# IoT_Greenhouse_V1_0_A_-_Esp32.net
KiCad netlist of a schematic drawn in Altium Designer
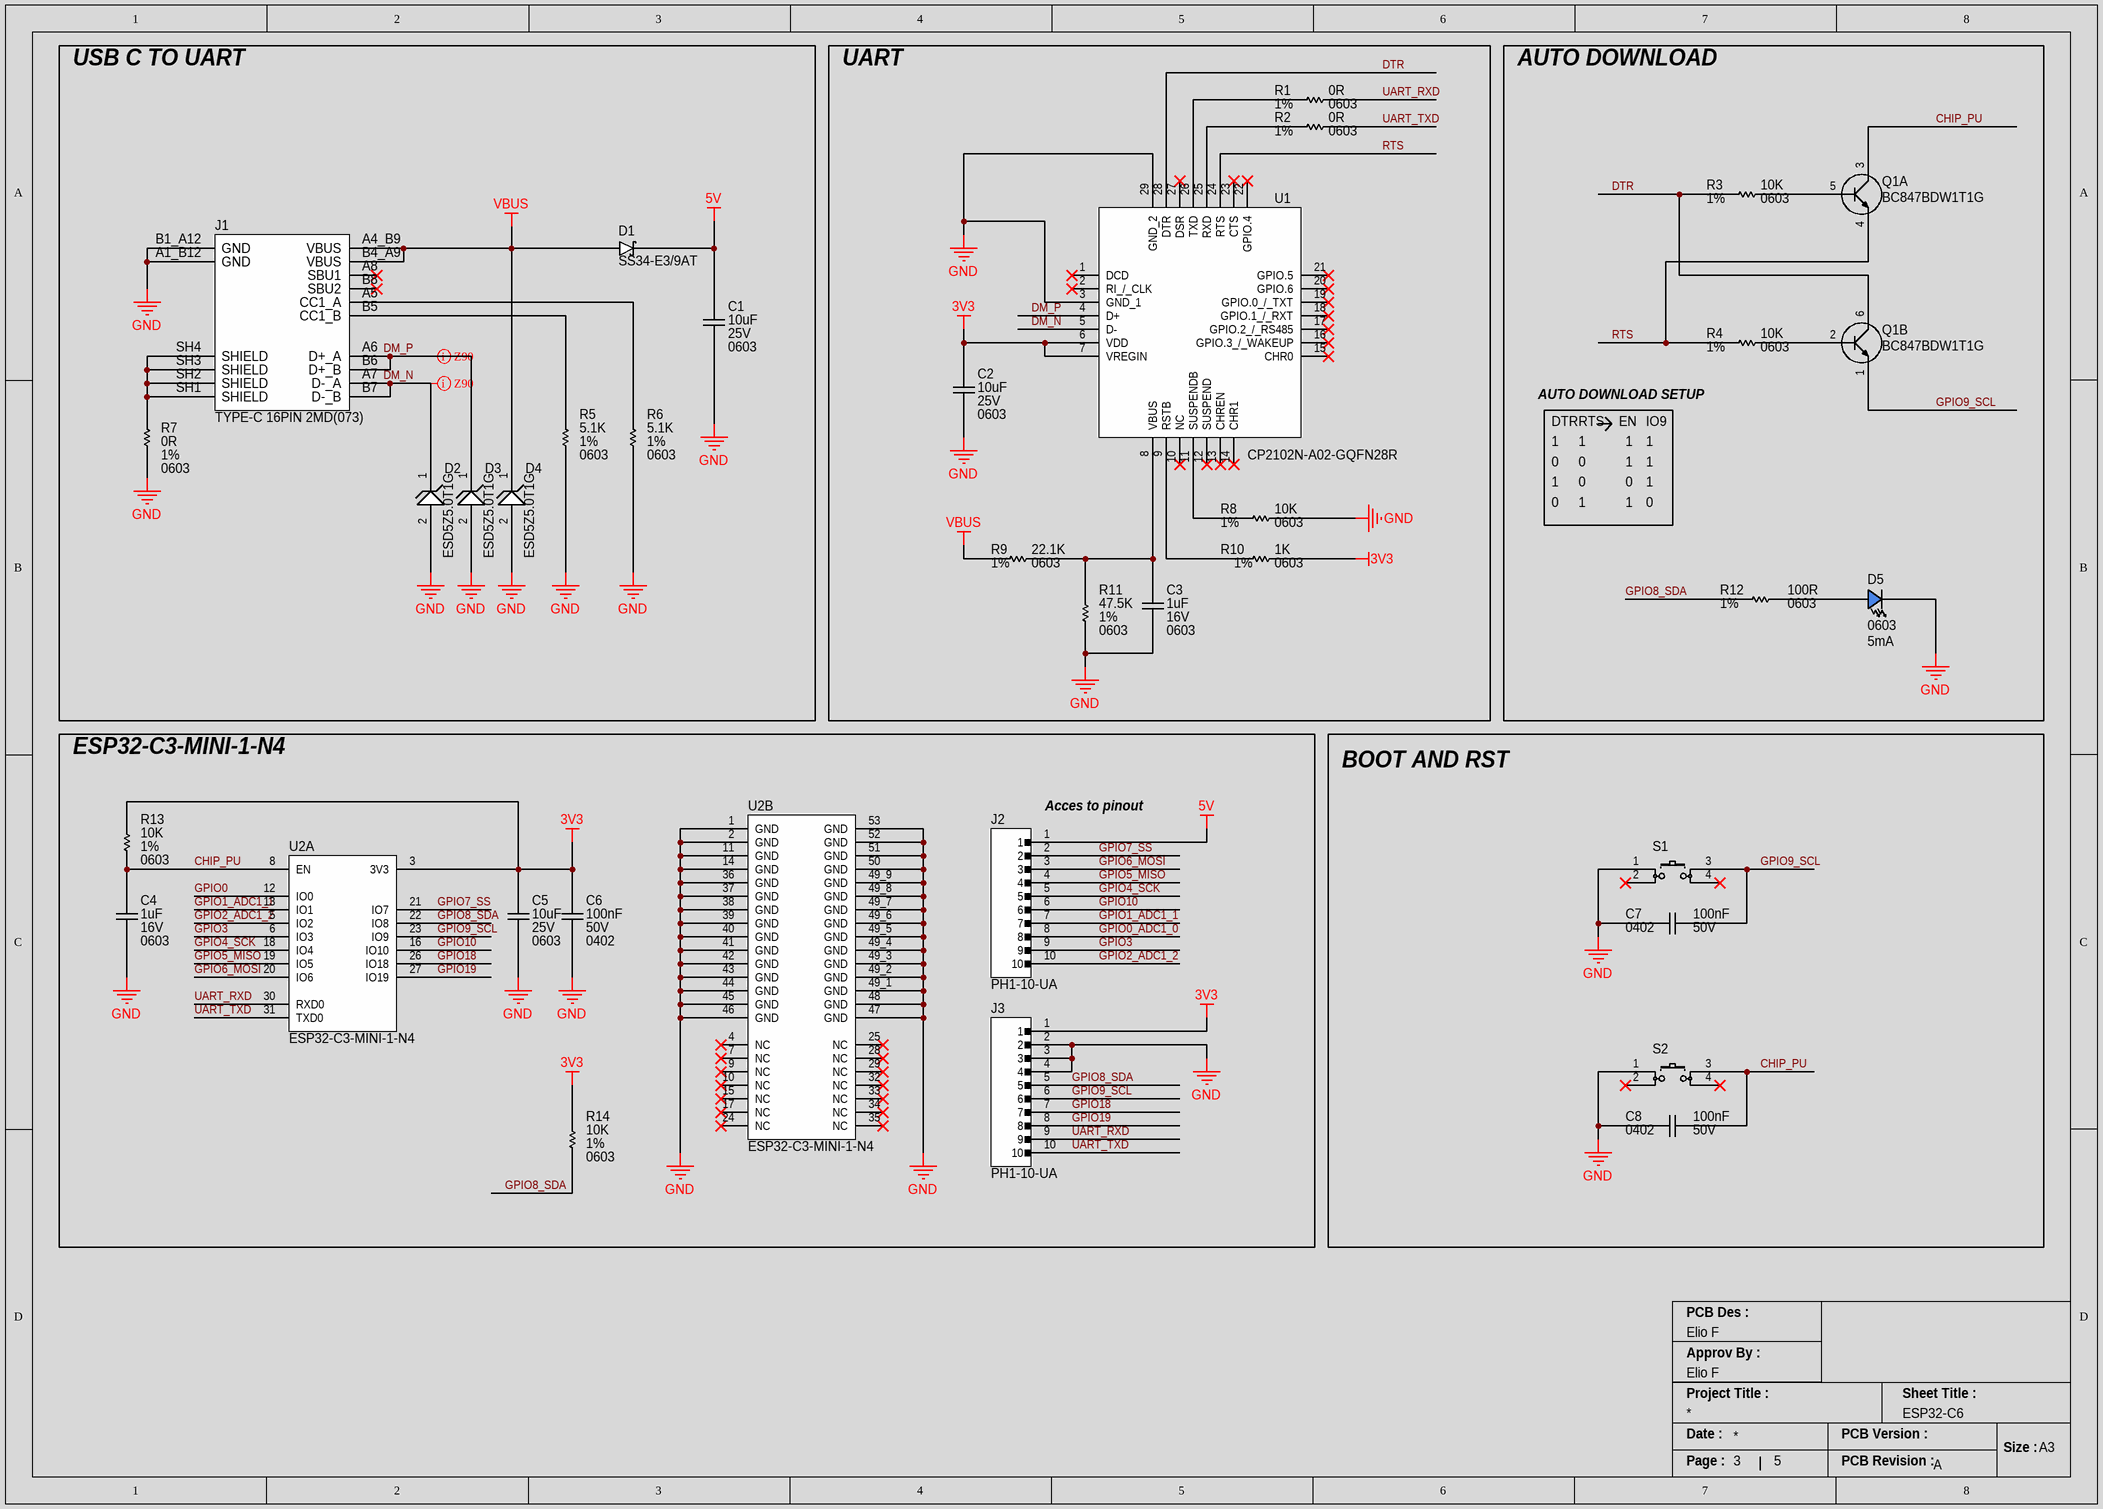
[diagram p0: IoT_Greenhouse V1.0 A - Esp32.SchDoc]

(export (version "E")
  (design (tool "Eeschema 10.0.6"))
  (components
    (comp (ref "C1")
      (value "GRM188R61E106MA73D")
      (footprint "CAP_0603_CAPC1608X08N")
      (description "Multilayer Ceramic Capacitor, 10 uF, 25 V, ± 20%, X5R, 0603 [1608 Metric]")
      (fields
        (field (name "MANUFACTURER") "Murata")
        (field (name "TOLERANCE") "20%")
        (field (name "CASE/PACKAGE") "0603")
        (field (name "CAPACITANCE") "10uF")
        (field (name "VOLTAGE RATING") "25V")
      )
      (libsource (lib "Electronic Devices_LIB") (part "CAP_10UF_25V_X5R_0603"))
    )
    (comp (ref "C2")
      (value "GRM188R61E106MA73D")
      (footprint "CAP_0603_CAPC1608X08N")
      (description "Multilayer Ceramic Capacitor, 10 uF, 25 V, ± 20%, X5R, 0603 [1608 Metric]")
      (fields
        (field (name "MANUFACTURER") "Murata")
        (field (name "TOLERANCE") "20%")
        (field (name "CASE/PACKAGE") "0603")
        (field (name "CAPACITANCE") "10uF")
        (field (name "VOLTAGE RATING") "25V")
      )
      (libsource (lib "Electronic Devices_LIB") (part "CAP_10UF_25V_X5R_0603"))
    )
    (comp (ref "C3")
      (value "CL10A105KO8NNNC")
      (footprint "CAP_0603_CAPC1608X08N")
      (description "CAP CER 1UF 16V X5R 0603")
      (fields
        (field (name "MANUFACTURER") "Samsung")
        (field (name "TOLERANCE") "10%")
        (field (name "VOLTAGE RATING") "16V")
        (field (name "CAPACITANCE") "1uF")
        (field (name "CASE/PACKAGE") "0603")
      )
      (libsource (lib "Electronic Devices_LIB") (part "CAP_1UF_16V_X5R_0603"))
    )
    (comp (ref "C4")
      (value "CL10A105KO8NNNC")
      (footprint "CAP_0603_CAPC1608X08N")
      (description "CAP CER 1UF 16V X5R 0603")
      (fields
        (field (name "MANUFACTURER") "Samsung")
        (field (name "TOLERANCE") "10%")
        (field (name "VOLTAGE RATING") "16V")
        (field (name "CAPACITANCE") "1uF")
        (field (name "CASE/PACKAGE") "0603")
      )
      (libsource (lib "Electronic Devices_LIB") (part "CAP_1UF_16V_X5R_0603"))
    )
    (comp (ref "C5")
      (value "GRM188R61E106MA73D")
      (footprint "CAP_0603_CAPC1608X08N")
      (description "Multilayer Ceramic Capacitor, 10 uF, 25 V, ± 20%, X5R, 0603 [1608 Metric]")
      (fields
        (field (name "MANUFACTURER") "Murata")
        (field (name "TOLERANCE") "20%")
        (field (name "CASE/PACKAGE") "0603")
        (field (name "CAPACITANCE") "10uF")
        (field (name "VOLTAGE RATING") "25V")
      )
      (libsource (lib "Electronic Devices_LIB") (part "CAP_10UF_25V_X5R_0603"))
    )
    (comp (ref "C6")
      (value "GRM155R71H104KE14D")
      (footprint "CAP_0402_CAPC1005X05N")
      (description "Multilayer Ceramic Capacitor, 0.1 uF, 16 V, ± 10%, X7R, 0402 [1005 Metric]")
      (fields
        (field (name "MANUFACTURER") "Murata")
        (field (name "TOLERANCE") "10%")
        (field (name "VOLTAGE RATING") "50V")
        (field (name "CAPACITANCE") "100nF")
        (field (name "CASE/PACKAGE") "0402")
      )
      (libsource (lib "Electronic Devices_LIB") (part "CAP_100NF_50V_X7R_0402"))
    )
    (comp (ref "C7")
      (value "GRM155R71H104KE14D")
      (footprint "CAP_0402_CAPC1005X05N")
      (description "Multilayer Ceramic Capacitor, 0.1 uF, 16 V, ± 10%, X7R, 0402 [1005 Metric]")
      (fields
        (field (name "MANUFACTURER") "Murata")
        (field (name "TOLERANCE") "10%")
        (field (name "VOLTAGE RATING") "50V")
        (field (name "CAPACITANCE") "100nF")
        (field (name "CASE/PACKAGE") "0402")
      )
      (libsource (lib "Electronic Devices_LIB") (part "CAP_100NF_50V_X7R_0402"))
    )
    (comp (ref "C8")
      (value "GRM155R71H104KE14D")
      (footprint "CAP_0402_CAPC1005X05N")
      (description "Multilayer Ceramic Capacitor, 0.1 uF, 16 V, ± 10%, X7R, 0402 [1005 Metric]")
      (fields
        (field (name "MANUFACTURER") "Murata")
        (field (name "TOLERANCE") "10%")
        (field (name "VOLTAGE RATING") "50V")
        (field (name "CAPACITANCE") "100nF")
        (field (name "CASE/PACKAGE") "0402")
      )
      (libsource (lib "Electronic Devices_LIB") (part "CAP_100NF_50V_X7R_0402"))
    )
    (comp (ref "D1")
      (value "SS34-E3/9AT")
      (footprint "DIO_Vishay_SMC_MFG")
      (description "Rectifier Diode, schottky, 40V V(Rrm), do-214Ab / Smc")
      (fields (field (name "MANUFACTURER") "Vishay Semiconductors"))
      (libsource (lib "Electronic Devices_LIB") (part "DIO_SCTKY_40V_3A"))
    )
    (comp (ref "D2")
      (value "ESD5Z5.0T1G")
      (footprint "SOD523_SODFL1608X70N")
      (description "ESD5Z Series 6.2 V 80 pF 5 Vrwm TVS and ESD Protection Diodes - SOD-523")
      (fields (field (name "MANUFACTURER") "ON Semiconductor"))
      (libsource (lib "Electronic Devices_LIB") (part "DIO_TVS_5V_ESD5Z5.0T1G"))
    )
    (comp (ref "D3")
      (value "ESD5Z5.0T1G")
      (footprint "SOD523_SODFL1608X70N")
      (description "ESD5Z Series 6.2 V 80 pF 5 Vrwm TVS and ESD Protection Diodes - SOD-523")
      (fields (field (name "MANUFACTURER") "ON Semiconductor"))
      (libsource (lib "Electronic Devices_LIB") (part "DIO_TVS_5V_ESD5Z5.0T1G"))
    )
    (comp (ref "D4")
      (value "ESD5Z5.0T1G")
      (footprint "SOD523_SODFL1608X70N")
      (description "ESD5Z Series 6.2 V 80 pF 5 Vrwm TVS and ESD Protection Diodes - SOD-523")
      (fields (field (name "MANUFACTURER") "ON Semiconductor"))
      (libsource (lib "Electronic Devices_LIB") (part "DIO_TVS_5V_ESD5Z5.0T1G"))
    )
    (comp (ref "D5")
      (value "LTST-C193TBKT-5A")
      (footprint "LED_0603-BLUE-0.75mm")
      (description "LED Uni-Color Blue 468nm 2-Pin Chip LED T/R")
      (fields
        (field (name "MANUFACTURER") "Vishay Lite-On")
        (field (name "CASE CODE (IMPERIAL)") "0603")
        (field (name "TEST CURRENT") "5mA")
      )
      (libsource (lib "Electronic Devices_LIB") (part "LED_DIO_BLUE_5mA_0603"))
    )
    (comp (ref "J1")
      (value "TYPE-C 16PIN 2MD(073)")
      (footprint "CONN_USB_C_16P")
      (description "5A 1 Surface Mount 16P Female -25℃~+85℃ Type-C SMD USB Connectors ROHS")
      (fields (field (name "MANUFACTURER") "SHOU HAN"))
      (libsource (lib "Electronic Devices_LIB") (part "CONN_USB_TYPEC_2.0_16P_TYPE-C 16PIN 2MD(073)"))
    )
    (comp (ref "J2")
      (value "PH1-10-UA")
      (footprint "CONN_HEADER_MALE_10P")
      (description "Conn Unshrouded Header HDR 12 POS 2.54mm Solder RA Side Entry Thru-Hole Bag")
      (fields (field (name "MANUFACTURER") "Adam Equipment"))
      (libsource (lib "Electronic Devices_LIB") (part "CONN_HEADER_MALE_10P_2.54mm_PH1-10-UA"))
    )
    (comp (ref "J3")
      (value "PH1-10-UA")
      (footprint "CONN_HEADER_MALE_10P")
      (description "Conn Unshrouded Header HDR 12 POS 2.54mm Solder RA Side Entry Thru-Hole Bag")
      (fields (field (name "MANUFACTURER") "Adam Equipment"))
      (libsource (lib "Electronic Devices_LIB") (part "CONN_HEADER_MALE_10P_2.54mm_PH1-10-UA"))
    )
    (comp (ref "Q1")
      (value "BC847BDW1T1G")
      (footprint "TRANS_BJT_SOT65P210X110-6N")
      (description "ON Semi BC847BDW1T1G Dual NPN Bipolar Transistor; 0.1 A; 45 V; 6-Pin SC-88")
      (fields (field (name "MANUFACTURER") "ON Semiconductor"))
      (libsource (lib "Electronic Devices_LIB") (part "TRANS_BIPOLAR_NPN_BC847BDW1T1G"))
    )
    (comp (ref "R1")
      (value "RC0603FR-070RL")
      (footprint "RES_0603_RESC1608X04N")
      (description "RC Series 0603 0.1 W 0 Ohm Jumper Surface Mount Thick Film Chip Resistor")
      (fields
        (field (name "MANUFACTURER") "Yageo")
        (field (name "TOLERANCE") "1%")
        (field (name "RESISTANCE") "0R")
        (field (name "CASE CODE (IMPERIAL)") "0603")
      )
      (libsource (lib "Electronic Devices_LIB") (part "RES_0R_1%_100mW_0603"))
    )
    (comp (ref "R2")
      (value "RC0603FR-070RL")
      (footprint "RES_0603_RESC1608X04N")
      (description "RC Series 0603 0.1 W 0 Ohm Jumper Surface Mount Thick Film Chip Resistor")
      (fields
        (field (name "MANUFACTURER") "Yageo")
        (field (name "TOLERANCE") "1%")
        (field (name "RESISTANCE") "0R")
        (field (name "CASE CODE (IMPERIAL)") "0603")
      )
      (libsource (lib "Electronic Devices_LIB") (part "RES_0R_1%_100mW_0603"))
    )
    (comp (ref "R3")
      (value "AC0603FR-1010KL")
      (footprint "RES_0603_RESC1608X04N")
      (description "Chip Resistor Automotive Grade Thick Film 0603 10kOhm 1% Paper T/R")
      (fields
        (field (name "MANUFACTURER") "Yageo")
        (field (name "RESISTANCE") "10K")
        (field (name "TOLERANCE") "1%")
        (field (name "CASE/PACKAGE") "0603")
      )
      (libsource (lib "Electronic Devices_LIB") (part "RES_10K_1%_100mW_0603"))
    )
    (comp (ref "R4")
      (value "AC0603FR-1010KL")
      (footprint "RES_0603_RESC1608X04N")
      (description "Chip Resistor Automotive Grade Thick Film 0603 10kOhm 1% Paper T/R")
      (fields
        (field (name "MANUFACTURER") "Yageo")
        (field (name "RESISTANCE") "10K")
        (field (name "TOLERANCE") "1%")
        (field (name "CASE/PACKAGE") "0603")
      )
      (libsource (lib "Electronic Devices_LIB") (part "RES_10K_1%_100mW_0603"))
    )
    (comp (ref "R5")
      (value "RC0603FR-075K1L")
      (footprint "RES_0603_RESC1608X04N")
      (description "SMD Chip Resistor, 5.1 kOhm, ± 1%, 100 mW, 0603 [1608 Metric], Thick Film, General Purpose")
      (fields
        (field (name "MANUFACTURER") "Yageo")
        (field (name "TOLERANCE") "1%")
        (field (name "RESISTANCE") "5.1K")
        (field (name "CASE/PACKAGE") "0603")
      )
      (libsource (lib "Electronic Devices_LIB") (part "RES_5.1K_1%_100mW_0603"))
    )
    (comp (ref "R6")
      (value "RC0603FR-075K1L")
      (footprint "RES_0603_RESC1608X04N")
      (description "SMD Chip Resistor, 5.1 kOhm, ± 1%, 100 mW, 0603 [1608 Metric], Thick Film, General Purpose")
      (fields
        (field (name "MANUFACTURER") "Yageo")
        (field (name "TOLERANCE") "1%")
        (field (name "RESISTANCE") "5.1K")
        (field (name "CASE/PACKAGE") "0603")
      )
      (libsource (lib "Electronic Devices_LIB") (part "RES_5.1K_1%_100mW_0603"))
    )
    (comp (ref "R7")
      (value "RC0603FR-070RL")
      (footprint "RES_0603_RESC1608X04N")
      (description "RC Series 0603 0.1 W 0 Ohm Jumper Surface Mount Thick Film Chip Resistor")
      (fields
        (field (name "MANUFACTURER") "Yageo")
        (field (name "TOLERANCE") "1%")
        (field (name "RESISTANCE") "0R")
        (field (name "CASE CODE (IMPERIAL)") "0603")
      )
      (libsource (lib "Electronic Devices_LIB") (part "RES_0R_1%_100mW_0603"))
    )
    (comp (ref "R8")
      (value "AC0603FR-1010KL")
      (footprint "RES_0603_RESC1608X04N")
      (description "Chip Resistor Automotive Grade Thick Film 0603 10kOhm 1% Paper T/R")
      (fields
        (field (name "MANUFACTURER") "Yageo")
        (field (name "RESISTANCE") "10K")
        (field (name "TOLERANCE") "1%")
        (field (name "CASE/PACKAGE") "0603")
      )
      (libsource (lib "Electronic Devices_LIB") (part "RES_10K_1%_100mW_0603"))
    )
    (comp (ref "R9")
      (value "RC0603FR-0722K1L")
      (footprint "RES_0603_RESC1608X04N")
      (description "SMD Chip Resistor, 22.1 kOhm, ± 1%, 100 mW, 0603 [1608 Metric], Thick Film, General Purpose")
      (fields
        (field (name "MANUFACTURER") "Yageo")
        (field (name "RESISTANCE") "22.1K")
        (field (name "TOLERANCE") "1%")
        (field (name "CASE/PACKAGE") "0603")
      )
      (libsource (lib "Electronic Devices_LIB") (part "RES_22.1K_1%_100mW_0603"))
    )
    (comp (ref "R10")
      (value "AC0603FR-101KL")
      (footprint "RES_0603_RESC1608X04N")
      (description "Chip Resistor Automotive Grade Thick Film 0603 1kOhm 1% Paper T/R")
      (fields
        (field (name "MANUFACTURER") "Yageo")
        (field (name "RESISTANCE") "1K")
        (field (name "TOLERANCE") "1%")
        (field (name "CASE/PACKAGE") "0603")
      )
      (libsource (lib "Electronic Devices_LIB") (part "RES_1K_1%_100mW_0603"))
    )
    (comp (ref "R11")
      (value "AC0603FR-0747K5L")
      (footprint "RES_0603_RESC1608X04N")
      (description "SMD Chip Resistor, 47.5 kOhm, ± 1%, 100 mW, 0603 [1608 Metric], Thick Film, General Purpose")
      (fields
        (field (name "MANUFACTURER") "Yageo")
        (field (name "TOLERANCE") "1%")
        (field (name "RESISTANCE") "47.5K")
        (field (name "CASE/PACKAGE") "0603")
      )
      (libsource (lib "Electronic Devices_LIB") (part "RES_47.5K_1%_100mW_0603"))
    )
    (comp (ref "R12")
      (value "ERJ3EKF1000V")
      (footprint "CAP_0603_CAPC1608X08N")
      (description "Res Thick Film 0603 100 Ohm 1% 1/10W ±100ppm/°C Molded SMD Punched Carrier T/R")
      (fields
        (field (name "MANUFACTURER") "Panasonic")
        (field (name "CASE CODE (IMPERIAL)") "0603")
        (field (name "TOLERANCE") "1%")
        (field (name "RESISTANCE") "100R")
      )
      (libsource (lib "Electronic Devices_LIB") (part "RES_100R_1%_100MW_0603"))
    )
    (comp (ref "R13")
      (value "AC0603FR-1010KL")
      (footprint "RES_0603_RESC1608X04N")
      (description "Chip Resistor Automotive Grade Thick Film 0603 10kOhm 1% Paper T/R")
      (fields
        (field (name "MANUFACTURER") "Yageo")
        (field (name "RESISTANCE") "10K")
        (field (name "TOLERANCE") "1%")
        (field (name "CASE/PACKAGE") "0603")
      )
      (libsource (lib "Electronic Devices_LIB") (part "RES_10K_1%_100mW_0603"))
    )
    (comp (ref "R14")
      (value "AC0603FR-1010KL")
      (footprint "RES_0603_RESC1608X04N")
      (description "Chip Resistor Automotive Grade Thick Film 0603 10kOhm 1% Paper T/R")
      (fields
        (field (name "MANUFACTURER") "Yageo")
        (field (name "RESISTANCE") "10K")
        (field (name "TOLERANCE") "1%")
        (field (name "CASE/PACKAGE") "0603")
      )
      (libsource (lib "Electronic Devices_LIB") (part "RES_10K_1%_100mW_0603"))
    )
    (comp (ref "S1")
      (value "PTS526SK15SMTR2LFS")
      (footprint "SWT_NO_PTS526SK15SMTR2LFS")
      (description "Switch Tactile N.O. SPST Round Button Gull Wing 0.05A 12VDC 200000Cycles 2.55N SMD T/R")
      (fields (field (name "MANUFACTURER") "ITT C&K"))
      (libsource (lib "Electronic Devices_LIB") (part "SWITCH_NO_SPST_0.05A"))
    )
    (comp (ref "S2")
      (value "PTS526SK15SMTR2LFS")
      (footprint "SWT_NO_PTS526SK15SMTR2LFS")
      (description "Switch Tactile N.O. SPST Round Button Gull Wing 0.05A 12VDC 200000Cycles 2.55N SMD T/R")
      (fields (field (name "MANUFACTURER") "ITT C&K"))
      (libsource (lib "Electronic Devices_LIB") (part "SWITCH_NO_SPST_0.05A"))
    )
    (comp (ref "U1")
      (value "CP2102N-A02-GQFN28R")
      (footprint "IC_BRIDGE_UART_QFN50P500X500X80-29N-D")
      (description "Full Speed USB to UART Bridge USB 2.0 3.3V T/R Automotive 28-Pin QFN EP")
      (fields (field (name "MANUFACTURER") "Silicon Labs"))
      (libsource (lib "Electronic Devices_LIB") (part "IC_BRIDGE_UART_CP2102N-A02-GQFN28R"))
    )
    (comp (ref "U2")
      (value "ESP32-C3-MINI-1-N4")
      (footprint "XCVR_ESP32-C3-MINI-1-N4")
      (description "Multiprotocol Modules SMD module, ESP32-C3FN4, PCB antenna, -40 C +85 C")
      (fields (field (name "MANUFACTURER") "Espressif Systems"))
      (libsource (lib "Electronic Devices_LIB") (part "IC_MODULE_ESP32-C3-MINI-1-N4"))
    )
  )
  (nets
    (net (code "1") (name "/CHIP_PU") (class "Default")
      (node (ref "C4") (pin "2") (pinfunction "2_2") (pintype "passive"))
      (node (ref "C8") (pin "1") (pinfunction "1_1") (pintype "passive"))
      (node (ref "Q1") (pin "3") (pinfunction "COLLECTOR_1_3") (pintype "passive"))
      (node (ref "R13") (pin "2") (pinfunction "2_2") (pintype "passive"))
      (node (ref "S2") (pin "3") (pinfunction "NO1_3") (pintype "passive"))
      (node (ref "U2") (pin "8") (pinfunction "EN_8") (pintype "passive"))
    )
    (net (code "2") (name "/DM_N") (class "Default")
      (node (ref "D2") (pin "1") (pinfunction "K_1") (pintype "passive"))
      (node (ref "J1") (pin "A7") (pinfunction "D-_A_A7") (pintype "passive"))
      (node (ref "J1") (pin "B7") (pinfunction "D-_B_B7") (pintype "passive"))
      (node (ref "U1") (pin "5") (pinfunction "D-_5") (pintype "passive"))
    )
    (net (code "3") (name "/DM_P") (class "Default")
      (node (ref "D3") (pin "1") (pinfunction "K_1") (pintype "passive"))
      (node (ref "J1") (pin "A6") (pinfunction "D+_A_A6") (pintype "passive"))
      (node (ref "J1") (pin "B6") (pinfunction "D+_B_B6") (pintype "passive"))
      (node (ref "U1") (pin "4") (pinfunction "D+_4") (pintype "passive"))
    )
    (net (code "4") (name "/DTR") (class "Default")
      (node (ref "Q1") (pin "6") (pinfunction "COLLECTOR_2_6") (pintype "passive"))
      (node (ref "R3") (pin "2") (pinfunction "2_2") (pintype "passive"))
      (node (ref "U1") (pin "28") (pinfunction "DTR_28") (pintype "passive"))
    )
    (net (code "5") (name "/GPIO0") (class "Default")
      (node (ref "U2") (pin "12") (pinfunction "IO0_12") (pintype "passive"))
    )
    (net (code "6") (name "/GPIO0_ADC1_0") (class "Default")
      (node (ref "J2") (pin "8") (pinfunction "8_8") (pintype "passive"))
    )
    (net (code "7") (name "/GPIO1_ADC1_1") (class "Default")
      (node (ref "J2") (pin "7") (pinfunction "7_7") (pintype "passive"))
      (node (ref "U2") (pin "13") (pinfunction "IO1_13") (pintype "passive"))
    )
    (net (code "8") (name "/GPIO2_ADC1_2") (class "Default")
      (node (ref "J2") (pin "10") (pinfunction "10_10") (pintype "passive"))
      (node (ref "U2") (pin "5") (pinfunction "IO2_5") (pintype "passive"))
    )
    (net (code "9") (name "/GPIO3") (class "Default")
      (node (ref "J2") (pin "9") (pinfunction "9_9") (pintype "passive"))
      (node (ref "U2") (pin "6") (pinfunction "IO3_6") (pintype "passive"))
    )
    (net (code "10") (name "/GPIO4_SCK") (class "Default")
      (node (ref "J2") (pin "5") (pinfunction "5_5") (pintype "passive"))
      (node (ref "U2") (pin "18") (pinfunction "IO4_18") (pintype "passive"))
    )
    (net (code "11") (name "/GPIO5_MISO") (class "Default")
      (node (ref "J2") (pin "4") (pinfunction "4_4") (pintype "passive"))
      (node (ref "U2") (pin "19") (pinfunction "IO5_19") (pintype "passive"))
    )
    (net (code "12") (name "/GPIO6_MOSI") (class "Default")
      (node (ref "J2") (pin "3") (pinfunction "3_3") (pintype "passive"))
      (node (ref "U2") (pin "20") (pinfunction "IO6_20") (pintype "passive"))
    )
    (net (code "13") (name "/GPIO7_SS") (class "Default")
      (node (ref "J2") (pin "2") (pinfunction "2_2") (pintype "passive"))
      (node (ref "U2") (pin "21") (pinfunction "IO7_21") (pintype "passive"))
    )
    (net (code "14") (name "/GPIO8_SDA") (class "Default")
      (node (ref "J3") (pin "5") (pinfunction "5_5") (pintype "passive"))
      (node (ref "R12") (pin "1") (pinfunction "1_1") (pintype "passive"))
      (node (ref "R14") (pin "2") (pinfunction "2_2") (pintype "passive"))
      (node (ref "U2") (pin "22") (pinfunction "IO8_22") (pintype "passive"))
    )
    (net (code "15") (name "/GPIO9_SCL") (class "Default")
      (node (ref "C7") (pin "1") (pinfunction "1_1") (pintype "passive"))
      (node (ref "J3") (pin "6") (pinfunction "6_6") (pintype "passive"))
      (node (ref "Q1") (pin "1") (pinfunction "EMITTER_2_1") (pintype "passive"))
      (node (ref "S1") (pin "3") (pinfunction "NO1_3") (pintype "passive"))
      (node (ref "U2") (pin "23") (pinfunction "IO9_23") (pintype "passive"))
    )
    (net (code "16") (name "/GPIO10") (class "Default")
      (node (ref "J2") (pin "6") (pinfunction "6_6") (pintype "passive"))
      (node (ref "U2") (pin "16") (pinfunction "IO10_16") (pintype "passive"))
    )
    (net (code "17") (name "/GPIO18") (class "Default")
      (node (ref "J3") (pin "7") (pinfunction "7_7") (pintype "passive"))
      (node (ref "U2") (pin "26") (pinfunction "IO18_26") (pintype "passive"))
    )
    (net (code "18") (name "/GPIO19") (class "Default")
      (node (ref "J3") (pin "8") (pinfunction "8_8") (pintype "passive"))
      (node (ref "U2") (pin "27") (pinfunction "IO19_27") (pintype "passive"))
    )
    (net (code "19") (name "/RTS") (class "Default")
      (node (ref "Q1") (pin "4") (pinfunction "EMITTER_1_4") (pintype "passive"))
      (node (ref "R4") (pin "2") (pinfunction "2_2") (pintype "passive"))
      (node (ref "U1") (pin "24") (pinfunction "RTS_24") (pintype "passive"))
    )
    (net (code "20") (name "/UART_RXD") (class "Default")
      (node (ref "J3") (pin "9") (pinfunction "9_9") (pintype "passive"))
      (node (ref "R1") (pin "1") (pinfunction "1_1") (pintype "passive"))
      (node (ref "U2") (pin "30") (pinfunction "RXD0_30") (pintype "passive"))
    )
    (net (code "21") (name "/UART_TXD") (class "Default")
      (node (ref "J3") (pin "10") (pinfunction "10_10") (pintype "passive"))
      (node (ref "R2") (pin "1") (pinfunction "1_1") (pintype "passive"))
      (node (ref "U2") (pin "31") (pinfunction "TXD0_31") (pintype "passive"))
    )
    (net (code "22") (name "3V3") (class "Default")
      (node (ref "C2") (pin "2") (pinfunction "2_2") (pintype "passive"))
      (node (ref "C5") (pin "2") (pinfunction "2_2") (pintype "passive"))
      (node (ref "C6") (pin "2") (pinfunction "2_2") (pintype "passive"))
      (node (ref "J3") (pin "1") (pinfunction "1_1") (pintype "passive"))
      (node (ref "R10") (pin "2") (pinfunction "2_2") (pintype "passive"))
      (node (ref "R13") (pin "1") (pinfunction "1_1") (pintype "passive"))
      (node (ref "R14") (pin "1") (pinfunction "1_1") (pintype "passive"))
      (node (ref "U1") (pin "6") (pinfunction "VDD_6") (pintype "passive"))
      (node (ref "U1") (pin "7") (pinfunction "VREGIN_7") (pintype "passive"))
      (node (ref "U2") (pin "3") (pinfunction "3V3_3") (pintype "passive"))
    )
    (net (code "23") (name "5V") (class "Default")
      (node (ref "C1") (pin "2") (pinfunction "2_2") (pintype "passive"))
      (node (ref "D1") (pin "1") (pinfunction "K_1") (pintype "passive"))
      (node (ref "J2") (pin "1") (pinfunction "1_1") (pintype "passive"))
    )
    (net (code "24") (name "GND") (class "Default")
      (node (ref "C1") (pin "1") (pinfunction "1_1") (pintype "passive"))
      (node (ref "C2") (pin "1") (pinfunction "1_1") (pintype "passive"))
      (node (ref "C3") (pin "1") (pinfunction "1_1") (pintype "passive"))
      (node (ref "C4") (pin "1") (pinfunction "1_1") (pintype "passive"))
      (node (ref "C5") (pin "1") (pinfunction "1_1") (pintype "passive"))
      (node (ref "C6") (pin "1") (pinfunction "1_1") (pintype "passive"))
      (node (ref "C7") (pin "2") (pinfunction "2_2") (pintype "passive"))
      (node (ref "C8") (pin "2") (pinfunction "2_2") (pintype "passive"))
      (node (ref "D2") (pin "2") (pinfunction "A_2") (pintype "passive"))
      (node (ref "D3") (pin "2") (pinfunction "A_2") (pintype "passive"))
      (node (ref "D4") (pin "2") (pinfunction "A_2") (pintype "passive"))
      (node (ref "D5") (pin "1") (pinfunction "C_1") (pintype "passive"))
      (node (ref "J1") (pin "A1_B12") (pinfunction "GND_A1_B12") (pintype "power_in"))
      (node (ref "J1") (pin "B1_A12") (pinfunction "GND_B1_A12") (pintype "power_in"))
      (node (ref "J3") (pin "2") (pinfunction "2_2") (pintype "passive"))
      (node (ref "J3") (pin "3") (pinfunction "3_3") (pintype "passive"))
      (node (ref "J3") (pin "4") (pinfunction "4_4") (pintype "passive"))
      (node (ref "R11") (pin "1") (pinfunction "1_1") (pintype "passive"))
      (node (ref "R5") (pin "1") (pinfunction "1_1") (pintype "passive"))
      (node (ref "R6") (pin "1") (pinfunction "1_1") (pintype "passive"))
      (node (ref "R7") (pin "1") (pinfunction "1_1") (pintype "passive"))
      (node (ref "R8") (pin "2") (pinfunction "2_2") (pintype "passive"))
      (node (ref "S1") (pin "1") (pinfunction "COM_1_1") (pintype "passive"))
      (node (ref "S2") (pin "1") (pinfunction "COM_1_1") (pintype "passive"))
      (node (ref "U1") (pin "29") (pinfunction "GND_2_29") (pintype "passive"))
      (node (ref "U1") (pin "3") (pinfunction "GND_1_3") (pintype "passive"))
      (node (ref "U2") (pin "1") (pinfunction "GND_1") (pintype "power_in"))
      (node (ref "U2") (pin "11") (pinfunction "GND_11") (pintype "power_in"))
      (node (ref "U2") (pin "14") (pinfunction "GND_14") (pintype "power_in"))
      (node (ref "U2") (pin "2") (pinfunction "GND_2") (pintype "power_in"))
      (node (ref "U2") (pin "36") (pinfunction "GND_36") (pintype "power_in"))
      (node (ref "U2") (pin "37") (pinfunction "GND_37") (pintype "power_in"))
      (node (ref "U2") (pin "38") (pinfunction "GND_38") (pintype "power_in"))
      (node (ref "U2") (pin "39") (pinfunction "GND_39") (pintype "power_in"))
      (node (ref "U2") (pin "40") (pinfunction "GND_40") (pintype "power_in"))
      (node (ref "U2") (pin "41") (pinfunction "GND_41") (pintype "power_in"))
      (node (ref "U2") (pin "42") (pinfunction "GND_42") (pintype "power_in"))
      (node (ref "U2") (pin "43") (pinfunction "GND_43") (pintype "power_in"))
      (node (ref "U2") (pin "44") (pinfunction "GND_44") (pintype "power_in"))
      (node (ref "U2") (pin "45") (pinfunction "GND_45") (pintype "power_in"))
      (node (ref "U2") (pin "46") (pinfunction "GND_46") (pintype "power_in"))
      (node (ref "U2") (pin "47") (pinfunction "GND_47") (pintype "power_in"))
      (node (ref "U2") (pin "48") (pinfunction "GND_48") (pintype "power_in"))
      (node (ref "U2") (pin "49_1") (pinfunction "GND_49_1") (pintype "power_in"))
      (node (ref "U2") (pin "49_2") (pinfunction "GND_49_2") (pintype "power_in"))
      (node (ref "U2") (pin "49_3") (pinfunction "GND_49_3") (pintype "power_in"))
      (node (ref "U2") (pin "49_4") (pinfunction "GND_49_4") (pintype "power_in"))
      (node (ref "U2") (pin "49_5") (pinfunction "GND_49_5") (pintype "power_in"))
      (node (ref "U2") (pin "49_6") (pinfunction "GND_49_6") (pintype "power_in"))
      (node (ref "U2") (pin "49_7") (pinfunction "GND_49_7") (pintype "power_in"))
      (node (ref "U2") (pin "49_8") (pinfunction "GND_49_8") (pintype "power_in"))
      (node (ref "U2") (pin "49_9") (pinfunction "GND_49_9") (pintype "power_in"))
      (node (ref "U2") (pin "50") (pinfunction "GND_50") (pintype "power_in"))
      (node (ref "U2") (pin "51") (pinfunction "GND_51") (pintype "power_in"))
      (node (ref "U2") (pin "52") (pinfunction "GND_52") (pintype "power_in"))
      (node (ref "U2") (pin "53") (pinfunction "GND_53") (pintype "power_in"))
    )
    (net (code "25") (name "Net-(D5-A)") (class "Default")
      (node (ref "D5") (pin "2") (pinfunction "A_2") (pintype "passive"))
      (node (ref "R12") (pin "2") (pinfunction "2_2") (pintype "passive"))
    )
    (net (code "26") (name "Net-(J1-CC1_A)") (class "Default")
      (node (ref "J1") (pin "A5") (pinfunction "CC1_A_A5") (pintype "passive"))
      (node (ref "R6") (pin "2") (pinfunction "2_2") (pintype "passive"))
    )
    (net (code "27") (name "Net-(J1-CC1_B)") (class "Default")
      (node (ref "J1") (pin "B5") (pinfunction "CC1_B_B5") (pintype "passive"))
      (node (ref "R5") (pin "2") (pinfunction "2_2") (pintype "passive"))
    )
    (net (code "28") (name "Net-(J1-SHIELD-PadSH1)") (class "Default")
      (node (ref "J1") (pin "SH1") (pinfunction "SHIELD_SH1") (pintype "passive"))
      (node (ref "J1") (pin "SH2") (pinfunction "SHIELD_SH2") (pintype "passive"))
      (node (ref "J1") (pin "SH3") (pinfunction "SHIELD_SH3") (pintype "passive"))
      (node (ref "J1") (pin "SH4") (pinfunction "SHIELD_SH4") (pintype "passive"))
      (node (ref "R7") (pin "2") (pinfunction "2_2") (pintype "passive"))
    )
    (net (code "29") (name "Net-(Q1A-BASE_1)") (class "Default")
      (node (ref "Q1") (pin "5") (pinfunction "BASE_1_5") (pintype "passive"))
      (node (ref "R3") (pin "1") (pinfunction "1_1") (pintype "passive"))
    )
    (net (code "30") (name "Net-(Q1B-BASE_2)") (class "Default")
      (node (ref "Q1") (pin "2") (pinfunction "BASE_2_2") (pintype "passive"))
      (node (ref "R4") (pin "1") (pinfunction "1_1") (pintype "passive"))
    )
    (net (code "31") (name "Net-(U1-RSTB)") (class "Default")
      (node (ref "R10") (pin "1") (pinfunction "1_1") (pintype "passive"))
      (node (ref "U1") (pin "9") (pinfunction "RSTB_9") (pintype "passive"))
    )
    (net (code "32") (name "Net-(U1-RXD)") (class "Default")
      (node (ref "R2") (pin "2") (pinfunction "2_2") (pintype "passive"))
      (node (ref "U1") (pin "25") (pinfunction "RXD_25") (pintype "passive"))
    )
    (net (code "33") (name "Net-(U1-SUSPENDB)") (class "Default")
      (node (ref "R8") (pin "1") (pinfunction "1_1") (pintype "passive"))
      (node (ref "U1") (pin "11") (pinfunction "SUSPENDB_11") (pintype "passive"))
    )
    (net (code "34") (name "Net-(U1-TXD)") (class "Default")
      (node (ref "R1") (pin "2") (pinfunction "2_2") (pintype "passive"))
      (node (ref "U1") (pin "26") (pinfunction "TXD_26") (pintype "passive"))
    )
    (net (code "35") (name "Net-(U1-VBUS)") (class "Default")
      (node (ref "C3") (pin "2") (pinfunction "2_2") (pintype "passive"))
      (node (ref "R11") (pin "2") (pinfunction "2_2") (pintype "passive"))
      (node (ref "R9") (pin "2") (pinfunction "2_2") (pintype "passive"))
      (node (ref "U1") (pin "8") (pinfunction "VBUS_8") (pintype "passive"))
    )
    (net (code "36") (name "VBUS") (class "Default")
      (node (ref "D1") (pin "2") (pinfunction "A_2") (pintype "passive"))
      (node (ref "D4") (pin "1") (pinfunction "K_1") (pintype "passive"))
      (node (ref "J1") (pin "A4_B9") (pinfunction "VBUS_A4_B9") (pintype "power_in"))
      (node (ref "J1") (pin "B4_A9") (pinfunction "VBUS_B4_A9") (pintype "power_in"))
      (node (ref "R9") (pin "1") (pinfunction "1_1") (pintype "passive"))
    )
    (net (code "37") (name "unconnected-(J1-SBU1-PadA8)") (class "Default")
      (node (ref "J1") (pin "A8") (pinfunction "SBU1_A8") (pintype "passive+no_connect"))
    )
    (net (code "38") (name "unconnected-(J1-SBU2-PadB8)") (class "Default")
      (node (ref "J1") (pin "B8") (pinfunction "SBU2_B8") (pintype "passive+no_connect"))
    )
    (net (code "39") (name "unconnected-(S1-COM2-Pad2)") (class "Default")
      (node (ref "S1") (pin "2") (pinfunction "COM2_2") (pintype "passive+no_connect"))
    )
    (net (code "40") (name "unconnected-(S1-NO2-Pad4)") (class "Default")
      (node (ref "S1") (pin "4") (pinfunction "NO2_4") (pintype "passive+no_connect"))
    )
    (net (code "41") (name "unconnected-(S2-COM2-Pad2)") (class "Default")
      (node (ref "S2") (pin "2") (pinfunction "COM2_2") (pintype "passive+no_connect"))
    )
    (net (code "42") (name "unconnected-(S2-NO2-Pad4)") (class "Default")
      (node (ref "S2") (pin "4") (pinfunction "NO2_4") (pintype "passive+no_connect"))
    )
    (net (code "43") (name "unconnected-(U1-CHR0-Pad15)") (class "Default")
      (node (ref "U1") (pin "15") (pinfunction "CHR0_15") (pintype "passive+no_connect"))
    )
    (net (code "44") (name "unconnected-(U1-CHR1-Pad14)") (class "Default")
      (node (ref "U1") (pin "14") (pinfunction "CHR1_14") (pintype "passive+no_connect"))
    )
    (net (code "45") (name "unconnected-(U1-CHREN-Pad13)") (class "Default")
      (node (ref "U1") (pin "13") (pinfunction "CHREN_13") (pintype "passive+no_connect"))
    )
    (net (code "46") (name "unconnected-(U1-CTS-Pad23)") (class "Default")
      (node (ref "U1") (pin "23") (pinfunction "CTS_23") (pintype "passive+no_connect"))
    )
    (net (code "47") (name "unconnected-(U1-DCD-Pad1)") (class "Default")
      (node (ref "U1") (pin "1") (pinfunction "DCD_1") (pintype "passive+no_connect"))
    )
    (net (code "48") (name "unconnected-(U1-DSR-Pad27)") (class "Default")
      (node (ref "U1") (pin "27") (pinfunction "DSR_27") (pintype "passive+no_connect"))
    )
    (net (code "49") (name "unconnected-(U1-GPIO.0_{slash}_TXT-Pad19)") (class "Default")
      (node (ref "U1") (pin "19") (pinfunction "GPIO.0_/_TXT_19") (pintype "passive+no_connect"))
    )
    (net (code "50") (name "unconnected-(U1-GPIO.1_{slash}_RXT-Pad18)") (class "Default")
      (node (ref "U1") (pin "18") (pinfunction "GPIO.1_/_RXT_18") (pintype "passive+no_connect"))
    )
    (net (code "51") (name "unconnected-(U1-GPIO.2_{slash}_RS485-Pad17)") (class "Default")
      (node (ref "U1") (pin "17") (pinfunction "GPIO.2_/_RS485_17") (pintype "passive+no_connect"))
    )
    (net (code "52") (name "unconnected-(U1-GPIO.3_{slash}_WAKEUP-Pad16)") (class "Default")
      (node (ref "U1") (pin "16") (pinfunction "GPIO.3_/_WAKEUP_16") (pintype "passive+no_connect"))
    )
    (net (code "53") (name "unconnected-(U1-GPIO.4-Pad22)") (class "Default")
      (node (ref "U1") (pin "22") (pinfunction "GPIO.4_22") (pintype "passive+no_connect"))
    )
    (net (code "54") (name "unconnected-(U1-GPIO.5-Pad21)") (class "Default")
      (node (ref "U1") (pin "21") (pinfunction "GPIO.5_21") (pintype "passive+no_connect"))
    )
    (net (code "55") (name "unconnected-(U1-GPIO.6-Pad20)") (class "Default")
      (node (ref "U1") (pin "20") (pinfunction "GPIO.6_20") (pintype "passive+no_connect"))
    )
    (net (code "56") (name "unconnected-(U1-NC-Pad10)") (class "Default")
      (node (ref "U1") (pin "10") (pinfunction "NC_10") (pintype "passive+no_connect"))
    )
    (net (code "57") (name "unconnected-(U1-RI_{slash}_CLK-Pad2)") (class "Default")
      (node (ref "U1") (pin "2") (pinfunction "RI_/_CLK_2") (pintype "passive+no_connect"))
    )
    (net (code "58") (name "unconnected-(U1-SUSPEND-Pad12)") (class "Default")
      (node (ref "U1") (pin "12") (pinfunction "SUSPEND_12") (pintype "passive+no_connect"))
    )
    (net (code "59") (name "unconnected-(U2B-NC-Pad4)") (class "Default")
      (node (ref "U2") (pin "4") (pinfunction "NC_4") (pintype "passive+no_connect"))
    )
    (net (code "60") (name "unconnected-(U2B-NC-Pad7)") (class "Default")
      (node (ref "U2") (pin "7") (pinfunction "NC_7") (pintype "passive+no_connect"))
    )
    (net (code "61") (name "unconnected-(U2B-NC-Pad9)") (class "Default")
      (node (ref "U2") (pin "9") (pinfunction "NC_9") (pintype "passive+no_connect"))
    )
    (net (code "62") (name "unconnected-(U2B-NC-Pad10)") (class "Default")
      (node (ref "U2") (pin "10") (pinfunction "NC_10") (pintype "passive+no_connect"))
    )
    (net (code "63") (name "unconnected-(U2B-NC-Pad15)") (class "Default")
      (node (ref "U2") (pin "15") (pinfunction "NC_15") (pintype "passive+no_connect"))
    )
    (net (code "64") (name "unconnected-(U2B-NC-Pad17)") (class "Default")
      (node (ref "U2") (pin "17") (pinfunction "NC_17") (pintype "passive+no_connect"))
    )
    (net (code "65") (name "unconnected-(U2B-NC-Pad24)") (class "Default")
      (node (ref "U2") (pin "24") (pinfunction "NC_24") (pintype "passive+no_connect"))
    )
    (net (code "66") (name "unconnected-(U2B-NC-Pad25)") (class "Default")
      (node (ref "U2") (pin "25") (pinfunction "NC_25") (pintype "passive+no_connect"))
    )
    (net (code "67") (name "unconnected-(U2B-NC-Pad28)") (class "Default")
      (node (ref "U2") (pin "28") (pinfunction "NC_28") (pintype "passive+no_connect"))
    )
    (net (code "68") (name "unconnected-(U2B-NC-Pad29)") (class "Default")
      (node (ref "U2") (pin "29") (pinfunction "NC_29") (pintype "passive+no_connect"))
    )
    (net (code "69") (name "unconnected-(U2B-NC-Pad32)") (class "Default")
      (node (ref "U2") (pin "32") (pinfunction "NC_32") (pintype "passive+no_connect"))
    )
    (net (code "70") (name "unconnected-(U2B-NC-Pad33)") (class "Default")
      (node (ref "U2") (pin "33") (pinfunction "NC_33") (pintype "passive+no_connect"))
    )
    (net (code "71") (name "unconnected-(U2B-NC-Pad34)") (class "Default")
      (node (ref "U2") (pin "34") (pinfunction "NC_34") (pintype "passive+no_connect"))
    )
    (net (code "72") (name "unconnected-(U2B-NC-Pad35)") (class "Default")
      (node (ref "U2") (pin "35") (pinfunction "NC_35") (pintype "passive+no_connect"))
    )
  )
)
